# Car_Board.net
KiCad netlist of a schematic drawn in EAGLE
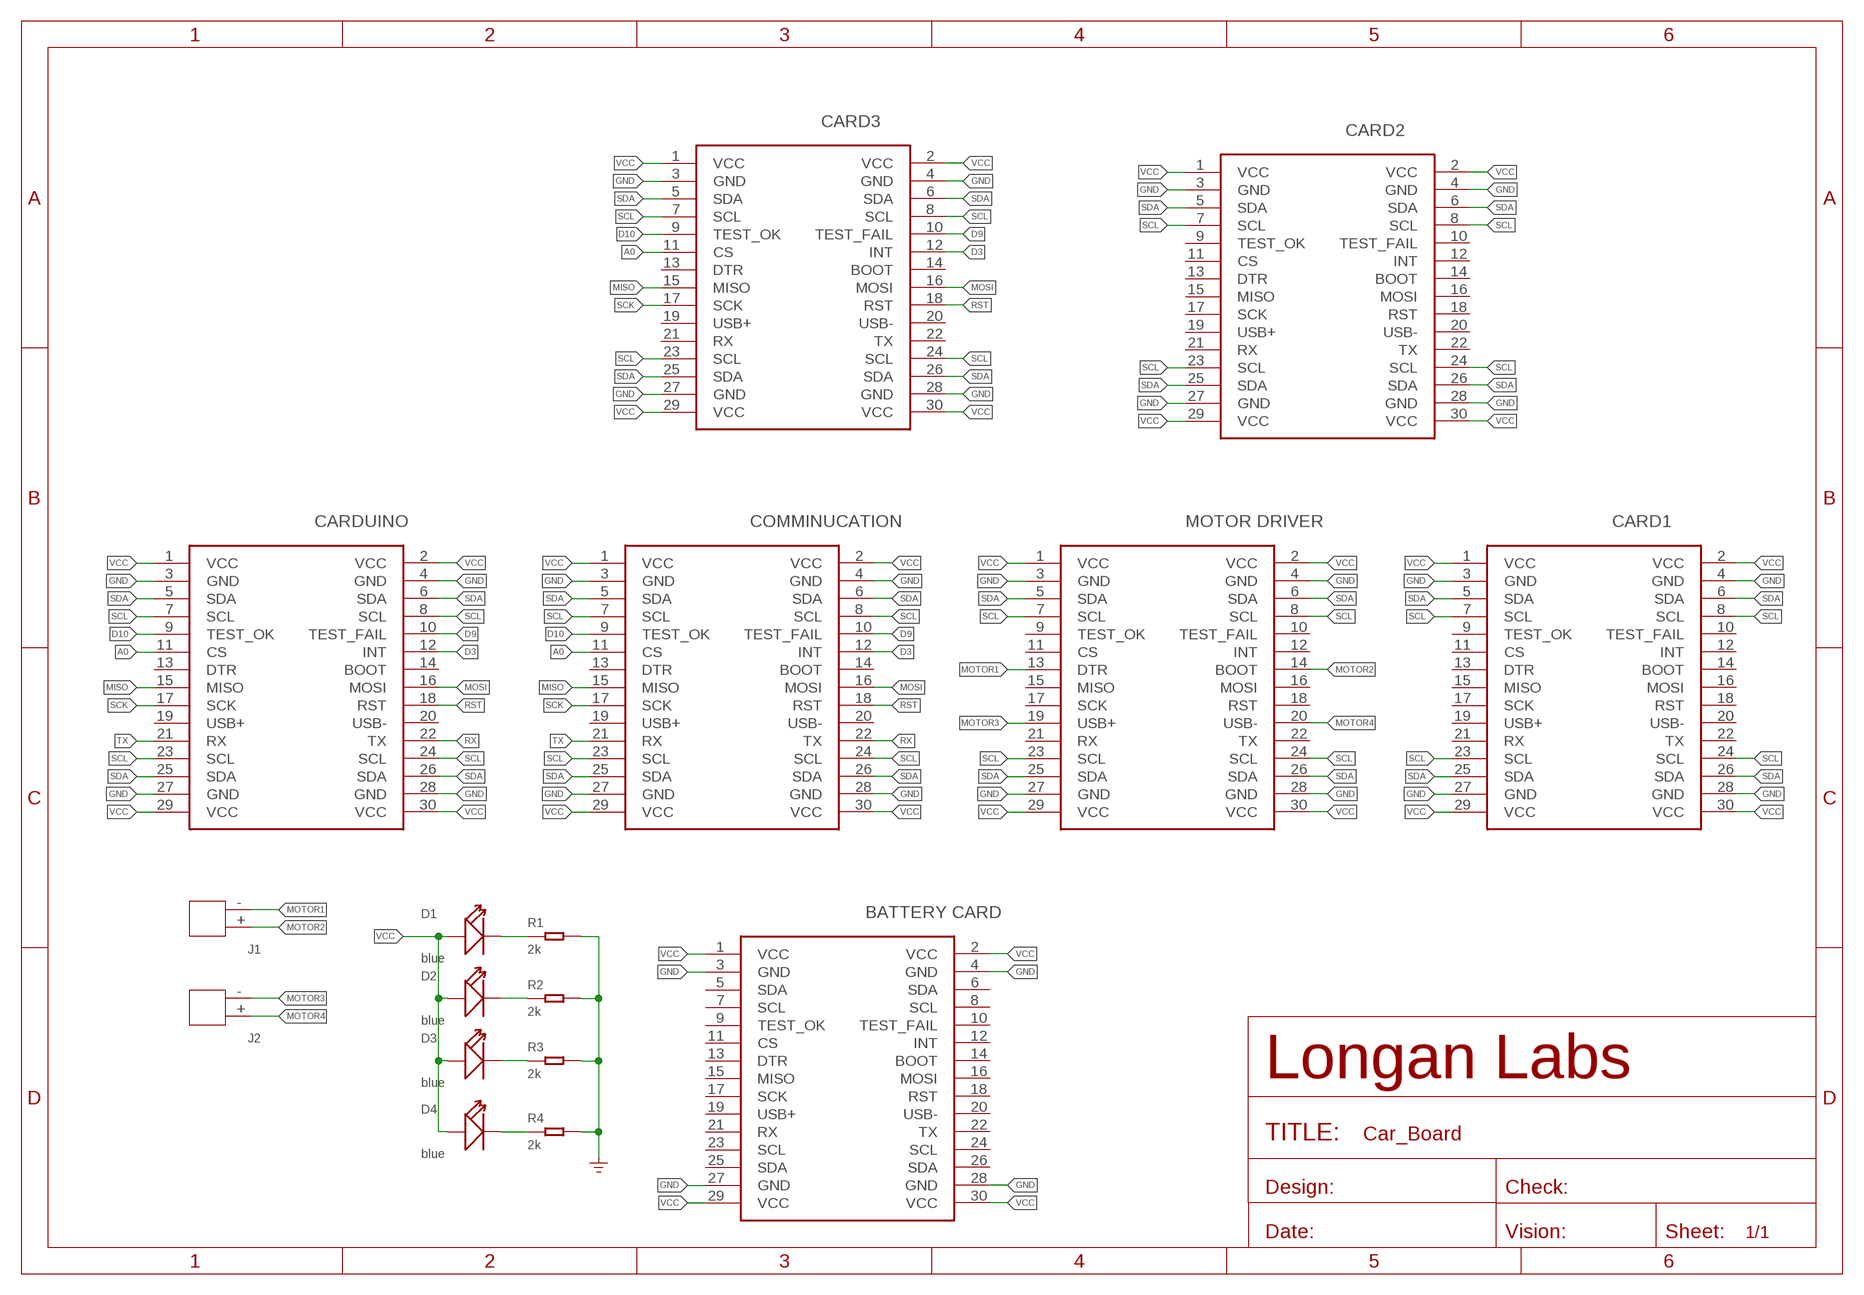
[diagram p0: schematic, sheet 1]

(export (version "E")
  (design (tool "Eeschema 10.0.6"))
  (components
    (comp (ref "CARDUINO")
      (value "CARDUINO")
      (footprint "eagle-import:2X15P-2.54")
      (libsource (lib "eagle-import") (part "MOUDLE-2X15P-2.54'2.54'"))
    )
    (comp (ref "CARDUINO1")
      (value "COMMINUCATION")
      (footprint "eagle-import:2X15P-2.54")
      (libsource (lib "eagle-import") (part "MOUDLE-2X15P-2.54'2.54'"))
    )
    (comp (ref "CARDUINO2")
      (value "MOTOR DRIVER")
      (footprint "eagle-import:2X15P-2.54")
      (libsource (lib "eagle-import") (part "MOUDLE-2X15P-2.54'2.54'"))
    )
    (comp (ref "CARDUINO3")
      (value "CARD1")
      (footprint "eagle-import:2X15P-2.54")
      (libsource (lib "eagle-import") (part "MOUDLE-2X15P-2.54'2.54'"))
    )
    (comp (ref "CARDUINO4")
      (value "CARD2")
      (footprint "eagle-import:2X15P-2.54")
      (libsource (lib "eagle-import") (part "MOUDLE-2X15P-2.54'2.54'"))
    )
    (comp (ref "CARDUINO5")
      (value "CARD3")
      (footprint "eagle-import:2X15P-2.54-90D")
      (libsource (lib "eagle-import") (part "MOUDLE-2X15P-2.54'90D'"))
    )
    (comp (ref "D1")
      (value "blue")
      (footprint "eagle-import:LED-0603")
      (libsource (lib "eagle-import") (part "LED'0603'"))
    )
    (comp (ref "D2")
      (value "blue")
      (footprint "eagle-import:LED-0603")
      (libsource (lib "eagle-import") (part "LED'0603'"))
    )
    (comp (ref "D3")
      (value "blue")
      (footprint "eagle-import:LED-0603")
      (libsource (lib "eagle-import") (part "LED'0603'"))
    )
    (comp (ref "D4")
      (value "blue")
      (footprint "eagle-import:LED-0603")
      (libsource (lib "eagle-import") (part "LED'0603'"))
    )
    (comp (ref "J1")
      (value "JST-2P-DIP'2.0'")
      (footprint "eagle-import:H2-2.0-6X4.5MM")
      (libsource (lib "eagle-import") (part "JST-2P-DIP'2.0'"))
    )
    (comp (ref "J2")
      (value "JST-2P-DIP'2.0'")
      (footprint "eagle-import:H2-2.0-6X4.5MM")
      (libsource (lib "eagle-import") (part "JST-2P-DIP'2.0'"))
    )
    (comp (ref "MOUDLE4")
      (value "BATTERY CARD")
      (footprint "eagle-import:2X15P-2.54")
      (libsource (lib "eagle-import") (part "MOUDLE-2X15P-2.54'2.54'"))
    )
    (comp (ref "R1")
      (value "2k")
      (footprint "eagle-import:R0603")
      (libsource (lib "eagle-import") (part "RES-0603"))
    )
    (comp (ref "R2")
      (value "2k")
      (footprint "eagle-import:R0603")
      (libsource (lib "eagle-import") (part "RES-0603"))
    )
    (comp (ref "R3")
      (value "2k")
      (footprint "eagle-import:R0603")
      (libsource (lib "eagle-import") (part "RES-0603"))
    )
    (comp (ref "R4")
      (value "2k")
      (footprint "eagle-import:R0603")
      (libsource (lib "eagle-import") (part "RES-0603"))
    )
  )
  (nets
    (net (code "1") (name "A0") (class "Default")
      (node (ref "CARDUINO") (pin "11") (pinfunction "CS_11") (pintype "bidirectional"))
      (node (ref "CARDUINO1") (pin "11") (pinfunction "CS_11") (pintype "bidirectional"))
      (node (ref "CARDUINO5") (pin "11") (pinfunction "CS_11") (pintype "bidirectional"))
    )
    (net (code "2") (name "D3") (class "Default")
      (node (ref "CARDUINO") (pin "12") (pinfunction "INT_12") (pintype "bidirectional"))
      (node (ref "CARDUINO1") (pin "12") (pinfunction "INT_12") (pintype "bidirectional"))
      (node (ref "CARDUINO5") (pin "12") (pinfunction "INT_12") (pintype "bidirectional"))
    )
    (net (code "3") (name "D9") (class "Default")
      (node (ref "CARDUINO") (pin "10") (pinfunction "TEST_FAIL_10") (pintype "bidirectional"))
      (node (ref "CARDUINO1") (pin "10") (pinfunction "TEST_FAIL_10") (pintype "bidirectional"))
      (node (ref "CARDUINO5") (pin "10") (pinfunction "TEST_FAIL_10") (pintype "bidirectional"))
    )
    (net (code "4") (name "D10") (class "Default")
      (node (ref "CARDUINO") (pin "9") (pinfunction "TEST_OK_9") (pintype "bidirectional"))
      (node (ref "CARDUINO1") (pin "9") (pinfunction "TEST_OK_9") (pintype "bidirectional"))
      (node (ref "CARDUINO5") (pin "9") (pinfunction "TEST_OK_9") (pintype "bidirectional"))
    )
    (net (code "5") (name "GND") (class "Default")
      (node (ref "CARDUINO") (pin "27") (pinfunction "GND_27") (pintype "bidirectional"))
      (node (ref "CARDUINO") (pin "28") (pinfunction "GND_28") (pintype "bidirectional"))
      (node (ref "CARDUINO") (pin "3") (pinfunction "GND_3") (pintype "bidirectional"))
      (node (ref "CARDUINO") (pin "4") (pinfunction "GND_4") (pintype "bidirectional"))
      (node (ref "CARDUINO1") (pin "27") (pinfunction "GND_27") (pintype "bidirectional"))
      (node (ref "CARDUINO1") (pin "28") (pinfunction "GND_28") (pintype "bidirectional"))
      (node (ref "CARDUINO1") (pin "3") (pinfunction "GND_3") (pintype "bidirectional"))
      (node (ref "CARDUINO1") (pin "4") (pinfunction "GND_4") (pintype "bidirectional"))
      (node (ref "CARDUINO2") (pin "27") (pinfunction "GND_27") (pintype "bidirectional"))
      (node (ref "CARDUINO2") (pin "28") (pinfunction "GND_28") (pintype "bidirectional"))
      (node (ref "CARDUINO2") (pin "3") (pinfunction "GND_3") (pintype "bidirectional"))
      (node (ref "CARDUINO2") (pin "4") (pinfunction "GND_4") (pintype "bidirectional"))
      (node (ref "CARDUINO3") (pin "27") (pinfunction "GND_27") (pintype "bidirectional"))
      (node (ref "CARDUINO3") (pin "28") (pinfunction "GND_28") (pintype "bidirectional"))
      (node (ref "CARDUINO3") (pin "3") (pinfunction "GND_3") (pintype "bidirectional"))
      (node (ref "CARDUINO3") (pin "4") (pinfunction "GND_4") (pintype "bidirectional"))
      (node (ref "CARDUINO4") (pin "27") (pinfunction "GND_27") (pintype "bidirectional"))
      (node (ref "CARDUINO4") (pin "28") (pinfunction "GND_28") (pintype "bidirectional"))
      (node (ref "CARDUINO4") (pin "3") (pinfunction "GND_3") (pintype "bidirectional"))
      (node (ref "CARDUINO4") (pin "4") (pinfunction "GND_4") (pintype "bidirectional"))
      (node (ref "CARDUINO5") (pin "27") (pinfunction "GND_27") (pintype "bidirectional"))
      (node (ref "CARDUINO5") (pin "28") (pinfunction "GND_28") (pintype "bidirectional"))
      (node (ref "CARDUINO5") (pin "3") (pinfunction "GND_3") (pintype "bidirectional"))
      (node (ref "CARDUINO5") (pin "4") (pinfunction "GND_4") (pintype "bidirectional"))
      (node (ref "MOUDLE4") (pin "27") (pinfunction "GND_27") (pintype "bidirectional"))
      (node (ref "MOUDLE4") (pin "28") (pinfunction "GND_28") (pintype "bidirectional"))
      (node (ref "MOUDLE4") (pin "3") (pinfunction "GND_3") (pintype "bidirectional"))
      (node (ref "MOUDLE4") (pin "4") (pinfunction "GND_4") (pintype "bidirectional"))
      (node (ref "R1") (pin "2") (pinfunction "2_2") (pintype "passive"))
      (node (ref "R2") (pin "2") (pinfunction "2_2") (pintype "passive"))
      (node (ref "R3") (pin "2") (pinfunction "2_2") (pintype "passive"))
      (node (ref "R4") (pin "2") (pinfunction "2_2") (pintype "passive"))
    )
    (net (code "6") (name "MISO") (class "Default")
      (node (ref "CARDUINO") (pin "15") (pinfunction "MISO_15") (pintype "bidirectional"))
      (node (ref "CARDUINO1") (pin "15") (pinfunction "MISO_15") (pintype "bidirectional"))
      (node (ref "CARDUINO5") (pin "15") (pinfunction "MISO_15") (pintype "bidirectional"))
    )
    (net (code "7") (name "MOSI") (class "Default")
      (node (ref "CARDUINO") (pin "16") (pinfunction "MOSI_16") (pintype "bidirectional"))
      (node (ref "CARDUINO1") (pin "16") (pinfunction "MOSI_16") (pintype "bidirectional"))
      (node (ref "CARDUINO5") (pin "16") (pinfunction "MOSI_16") (pintype "bidirectional"))
    )
    (net (code "8") (name "MOTOR1") (class "Default")
      (node (ref "CARDUINO2") (pin "13") (pinfunction "DTR_13") (pintype "bidirectional"))
      (node (ref "J1") (pin "-") (pinfunction "P$2_-") (pintype "bidirectional"))
    )
    (net (code "9") (name "MOTOR2") (class "Default")
      (node (ref "CARDUINO2") (pin "14") (pinfunction "BOOT_14") (pintype "bidirectional"))
      (node (ref "J1") (pin "+") (pinfunction "P$1_+") (pintype "bidirectional"))
    )
    (net (code "10") (name "MOTOR3") (class "Default")
      (node (ref "CARDUINO2") (pin "19") (pinfunction "USB+_19") (pintype "bidirectional"))
      (node (ref "J2") (pin "-") (pinfunction "P$2_-") (pintype "bidirectional"))
    )
    (net (code "11") (name "MOTOR4") (class "Default")
      (node (ref "CARDUINO2") (pin "20") (pinfunction "USB-_20") (pintype "bidirectional"))
      (node (ref "J2") (pin "+") (pinfunction "P$1_+") (pintype "bidirectional"))
    )
    (net (code "12") (name "Net-(D1-Pad-)") (class "Default")
      (node (ref "D1") (pin "-") (pinfunction "-_-") (pintype "passive"))
      (node (ref "R1") (pin "1") (pinfunction "1_1") (pintype "passive"))
    )
    (net (code "13") (name "Net-(D2-Pad-)") (class "Default")
      (node (ref "D2") (pin "-") (pinfunction "-_-") (pintype "passive"))
      (node (ref "R2") (pin "1") (pinfunction "1_1") (pintype "passive"))
    )
    (net (code "14") (name "Net-(D3-Pad-)") (class "Default")
      (node (ref "D3") (pin "-") (pinfunction "-_-") (pintype "passive"))
      (node (ref "R3") (pin "1") (pinfunction "1_1") (pintype "passive"))
    )
    (net (code "15") (name "Net-(D4-Pad-)") (class "Default")
      (node (ref "D4") (pin "-") (pinfunction "-_-") (pintype "passive"))
      (node (ref "R4") (pin "1") (pinfunction "1_1") (pintype "passive"))
    )
    (net (code "16") (name "RST") (class "Default")
      (node (ref "CARDUINO") (pin "18") (pinfunction "RST_18") (pintype "bidirectional"))
      (node (ref "CARDUINO1") (pin "18") (pinfunction "RST_18") (pintype "bidirectional"))
      (node (ref "CARDUINO5") (pin "18") (pinfunction "RST_18") (pintype "bidirectional"))
    )
    (net (code "17") (name "RX") (class "Default")
      (node (ref "CARDUINO") (pin "22") (pinfunction "TX_22") (pintype "bidirectional"))
      (node (ref "CARDUINO1") (pin "22") (pinfunction "TX_22") (pintype "bidirectional"))
    )
    (net (code "18") (name "SCK") (class "Default")
      (node (ref "CARDUINO") (pin "17") (pinfunction "SCK_17") (pintype "bidirectional"))
      (node (ref "CARDUINO1") (pin "17") (pinfunction "SCK_17") (pintype "bidirectional"))
      (node (ref "CARDUINO5") (pin "17") (pinfunction "SCK_17") (pintype "bidirectional"))
    )
    (net (code "19") (name "SCL") (class "Default")
      (node (ref "CARDUINO") (pin "23") (pinfunction "SCL_23") (pintype "bidirectional"))
      (node (ref "CARDUINO") (pin "24") (pinfunction "SCL_24") (pintype "bidirectional"))
      (node (ref "CARDUINO") (pin "7") (pinfunction "SCL_7") (pintype "bidirectional"))
      (node (ref "CARDUINO") (pin "8") (pinfunction "SCL_8") (pintype "bidirectional"))
      (node (ref "CARDUINO1") (pin "23") (pinfunction "SCL_23") (pintype "bidirectional"))
      (node (ref "CARDUINO1") (pin "24") (pinfunction "SCL_24") (pintype "bidirectional"))
      (node (ref "CARDUINO1") (pin "7") (pinfunction "SCL_7") (pintype "bidirectional"))
      (node (ref "CARDUINO1") (pin "8") (pinfunction "SCL_8") (pintype "bidirectional"))
      (node (ref "CARDUINO2") (pin "23") (pinfunction "SCL_23") (pintype "bidirectional"))
      (node (ref "CARDUINO2") (pin "24") (pinfunction "SCL_24") (pintype "bidirectional"))
      (node (ref "CARDUINO2") (pin "7") (pinfunction "SCL_7") (pintype "bidirectional"))
      (node (ref "CARDUINO2") (pin "8") (pinfunction "SCL_8") (pintype "bidirectional"))
      (node (ref "CARDUINO3") (pin "23") (pinfunction "SCL_23") (pintype "bidirectional"))
      (node (ref "CARDUINO3") (pin "24") (pinfunction "SCL_24") (pintype "bidirectional"))
      (node (ref "CARDUINO3") (pin "7") (pinfunction "SCL_7") (pintype "bidirectional"))
      (node (ref "CARDUINO3") (pin "8") (pinfunction "SCL_8") (pintype "bidirectional"))
      (node (ref "CARDUINO4") (pin "23") (pinfunction "SCL_23") (pintype "bidirectional"))
      (node (ref "CARDUINO4") (pin "24") (pinfunction "SCL_24") (pintype "bidirectional"))
      (node (ref "CARDUINO4") (pin "7") (pinfunction "SCL_7") (pintype "bidirectional"))
      (node (ref "CARDUINO4") (pin "8") (pinfunction "SCL_8") (pintype "bidirectional"))
      (node (ref "CARDUINO5") (pin "23") (pinfunction "SCL_23") (pintype "bidirectional"))
      (node (ref "CARDUINO5") (pin "24") (pinfunction "SCL_24") (pintype "bidirectional"))
      (node (ref "CARDUINO5") (pin "7") (pinfunction "SCL_7") (pintype "bidirectional"))
      (node (ref "CARDUINO5") (pin "8") (pinfunction "SCL_8") (pintype "bidirectional"))
    )
    (net (code "20") (name "SDA") (class "Default")
      (node (ref "CARDUINO") (pin "25") (pinfunction "SDA_25") (pintype "bidirectional"))
      (node (ref "CARDUINO") (pin "26") (pinfunction "SDA_26") (pintype "bidirectional"))
      (node (ref "CARDUINO") (pin "5") (pinfunction "SDA_5") (pintype "bidirectional"))
      (node (ref "CARDUINO") (pin "6") (pinfunction "SDA_6") (pintype "bidirectional"))
      (node (ref "CARDUINO1") (pin "25") (pinfunction "SDA_25") (pintype "bidirectional"))
      (node (ref "CARDUINO1") (pin "26") (pinfunction "SDA_26") (pintype "bidirectional"))
      (node (ref "CARDUINO1") (pin "5") (pinfunction "SDA_5") (pintype "bidirectional"))
      (node (ref "CARDUINO1") (pin "6") (pinfunction "SDA_6") (pintype "bidirectional"))
      (node (ref "CARDUINO2") (pin "25") (pinfunction "SDA_25") (pintype "bidirectional"))
      (node (ref "CARDUINO2") (pin "26") (pinfunction "SDA_26") (pintype "bidirectional"))
      (node (ref "CARDUINO2") (pin "5") (pinfunction "SDA_5") (pintype "bidirectional"))
      (node (ref "CARDUINO2") (pin "6") (pinfunction "SDA_6") (pintype "bidirectional"))
      (node (ref "CARDUINO3") (pin "25") (pinfunction "SDA_25") (pintype "bidirectional"))
      (node (ref "CARDUINO3") (pin "26") (pinfunction "SDA_26") (pintype "bidirectional"))
      (node (ref "CARDUINO3") (pin "5") (pinfunction "SDA_5") (pintype "bidirectional"))
      (node (ref "CARDUINO3") (pin "6") (pinfunction "SDA_6") (pintype "bidirectional"))
      (node (ref "CARDUINO4") (pin "25") (pinfunction "SDA_25") (pintype "bidirectional"))
      (node (ref "CARDUINO4") (pin "26") (pinfunction "SDA_26") (pintype "bidirectional"))
      (node (ref "CARDUINO4") (pin "5") (pinfunction "SDA_5") (pintype "bidirectional"))
      (node (ref "CARDUINO4") (pin "6") (pinfunction "SDA_6") (pintype "bidirectional"))
      (node (ref "CARDUINO5") (pin "25") (pinfunction "SDA_25") (pintype "bidirectional"))
      (node (ref "CARDUINO5") (pin "26") (pinfunction "SDA_26") (pintype "bidirectional"))
      (node (ref "CARDUINO5") (pin "5") (pinfunction "SDA_5") (pintype "bidirectional"))
      (node (ref "CARDUINO5") (pin "6") (pinfunction "SDA_6") (pintype "bidirectional"))
    )
    (net (code "21") (name "TX") (class "Default")
      (node (ref "CARDUINO") (pin "21") (pinfunction "RX_21") (pintype "bidirectional"))
      (node (ref "CARDUINO1") (pin "21") (pinfunction "RX_21") (pintype "bidirectional"))
    )
    (net (code "22") (name "VCC") (class "Default")
      (node (ref "CARDUINO") (pin "1") (pinfunction "VCC_1") (pintype "bidirectional"))
      (node (ref "CARDUINO") (pin "2") (pinfunction "VCC_2") (pintype "bidirectional"))
      (node (ref "CARDUINO") (pin "29") (pinfunction "VCC_29") (pintype "bidirectional"))
      (node (ref "CARDUINO") (pin "30") (pinfunction "VCC_30") (pintype "bidirectional"))
      (node (ref "CARDUINO1") (pin "1") (pinfunction "VCC_1") (pintype "bidirectional"))
      (node (ref "CARDUINO1") (pin "2") (pinfunction "VCC_2") (pintype "bidirectional"))
      (node (ref "CARDUINO1") (pin "29") (pinfunction "VCC_29") (pintype "bidirectional"))
      (node (ref "CARDUINO1") (pin "30") (pinfunction "VCC_30") (pintype "bidirectional"))
      (node (ref "CARDUINO2") (pin "1") (pinfunction "VCC_1") (pintype "bidirectional"))
      (node (ref "CARDUINO2") (pin "2") (pinfunction "VCC_2") (pintype "bidirectional"))
      (node (ref "CARDUINO2") (pin "29") (pinfunction "VCC_29") (pintype "bidirectional"))
      (node (ref "CARDUINO2") (pin "30") (pinfunction "VCC_30") (pintype "bidirectional"))
      (node (ref "CARDUINO3") (pin "1") (pinfunction "VCC_1") (pintype "bidirectional"))
      (node (ref "CARDUINO3") (pin "2") (pinfunction "VCC_2") (pintype "bidirectional"))
      (node (ref "CARDUINO3") (pin "29") (pinfunction "VCC_29") (pintype "bidirectional"))
      (node (ref "CARDUINO3") (pin "30") (pinfunction "VCC_30") (pintype "bidirectional"))
      (node (ref "CARDUINO4") (pin "1") (pinfunction "VCC_1") (pintype "bidirectional"))
      (node (ref "CARDUINO4") (pin "2") (pinfunction "VCC_2") (pintype "bidirectional"))
      (node (ref "CARDUINO4") (pin "29") (pinfunction "VCC_29") (pintype "bidirectional"))
      (node (ref "CARDUINO4") (pin "30") (pinfunction "VCC_30") (pintype "bidirectional"))
      (node (ref "CARDUINO5") (pin "1") (pinfunction "VCC_1") (pintype "bidirectional"))
      (node (ref "CARDUINO5") (pin "2") (pinfunction "VCC_2") (pintype "bidirectional"))
      (node (ref "CARDUINO5") (pin "29") (pinfunction "VCC_29") (pintype "bidirectional"))
      (node (ref "CARDUINO5") (pin "30") (pinfunction "VCC_30") (pintype "bidirectional"))
      (node (ref "D1") (pin "+") (pinfunction "+_+") (pintype "passive"))
      (node (ref "D2") (pin "+") (pinfunction "+_+") (pintype "passive"))
      (node (ref "D3") (pin "+") (pinfunction "+_+") (pintype "passive"))
      (node (ref "D4") (pin "+") (pinfunction "+_+") (pintype "passive"))
      (node (ref "MOUDLE4") (pin "1") (pinfunction "VCC_1") (pintype "bidirectional"))
      (node (ref "MOUDLE4") (pin "2") (pinfunction "VCC_2") (pintype "bidirectional"))
      (node (ref "MOUDLE4") (pin "29") (pinfunction "VCC_29") (pintype "bidirectional"))
      (node (ref "MOUDLE4") (pin "30") (pinfunction "VCC_30") (pintype "bidirectional"))
    )
    (net (code "23") (name "unconnected-(CARDUINO-BOOT-Pad14)") (class "Default")
      (node (ref "CARDUINO") (pin "14") (pinfunction "BOOT_14") (pintype "bidirectional"))
    )
    (net (code "24") (name "unconnected-(CARDUINO-DTR-Pad13)") (class "Default")
      (node (ref "CARDUINO") (pin "13") (pinfunction "DTR_13") (pintype "bidirectional"))
    )
    (net (code "25") (name "unconnected-(CARDUINO-USB+-Pad19)") (class "Default")
      (node (ref "CARDUINO") (pin "19") (pinfunction "USB+_19") (pintype "bidirectional"))
    )
    (net (code "26") (name "unconnected-(CARDUINO-USB--Pad20)") (class "Default")
      (node (ref "CARDUINO") (pin "20") (pinfunction "USB-_20") (pintype "bidirectional"))
    )
    (net (code "27") (name "unconnected-(CARDUINO1-BOOT-Pad14)") (class "Default")
      (node (ref "CARDUINO1") (pin "14") (pinfunction "BOOT_14") (pintype "bidirectional"))
    )
    (net (code "28") (name "unconnected-(CARDUINO1-DTR-Pad13)") (class "Default")
      (node (ref "CARDUINO1") (pin "13") (pinfunction "DTR_13") (pintype "bidirectional"))
    )
    (net (code "29") (name "unconnected-(CARDUINO1-USB+-Pad19)") (class "Default")
      (node (ref "CARDUINO1") (pin "19") (pinfunction "USB+_19") (pintype "bidirectional"))
    )
    (net (code "30") (name "unconnected-(CARDUINO1-USB--Pad20)") (class "Default")
      (node (ref "CARDUINO1") (pin "20") (pinfunction "USB-_20") (pintype "bidirectional"))
    )
    (net (code "31") (name "unconnected-(CARDUINO2-CS-Pad11)") (class "Default")
      (node (ref "CARDUINO2") (pin "11") (pinfunction "CS_11") (pintype "bidirectional"))
    )
    (net (code "32") (name "unconnected-(CARDUINO2-INT-Pad12)") (class "Default")
      (node (ref "CARDUINO2") (pin "12") (pinfunction "INT_12") (pintype "bidirectional"))
    )
    (net (code "33") (name "unconnected-(CARDUINO2-MISO-Pad15)") (class "Default")
      (node (ref "CARDUINO2") (pin "15") (pinfunction "MISO_15") (pintype "bidirectional"))
    )
    (net (code "34") (name "unconnected-(CARDUINO2-MOSI-Pad16)") (class "Default")
      (node (ref "CARDUINO2") (pin "16") (pinfunction "MOSI_16") (pintype "bidirectional"))
    )
    (net (code "35") (name "unconnected-(CARDUINO2-RST-Pad18)") (class "Default")
      (node (ref "CARDUINO2") (pin "18") (pinfunction "RST_18") (pintype "bidirectional"))
    )
    (net (code "36") (name "unconnected-(CARDUINO2-RX-Pad21)") (class "Default")
      (node (ref "CARDUINO2") (pin "21") (pinfunction "RX_21") (pintype "bidirectional"))
    )
    (net (code "37") (name "unconnected-(CARDUINO2-SCK-Pad17)") (class "Default")
      (node (ref "CARDUINO2") (pin "17") (pinfunction "SCK_17") (pintype "bidirectional"))
    )
    (net (code "38") (name "unconnected-(CARDUINO2-TEST_FAIL-Pad10)") (class "Default")
      (node (ref "CARDUINO2") (pin "10") (pinfunction "TEST_FAIL_10") (pintype "bidirectional"))
    )
    (net (code "39") (name "unconnected-(CARDUINO2-TEST_OK-Pad9)") (class "Default")
      (node (ref "CARDUINO2") (pin "9") (pinfunction "TEST_OK_9") (pintype "bidirectional"))
    )
    (net (code "40") (name "unconnected-(CARDUINO2-TX-Pad22)") (class "Default")
      (node (ref "CARDUINO2") (pin "22") (pinfunction "TX_22") (pintype "bidirectional"))
    )
    (net (code "41") (name "unconnected-(CARDUINO3-BOOT-Pad14)") (class "Default")
      (node (ref "CARDUINO3") (pin "14") (pinfunction "BOOT_14") (pintype "bidirectional"))
    )
    (net (code "42") (name "unconnected-(CARDUINO3-CS-Pad11)") (class "Default")
      (node (ref "CARDUINO3") (pin "11") (pinfunction "CS_11") (pintype "bidirectional"))
    )
    (net (code "43") (name "unconnected-(CARDUINO3-DTR-Pad13)") (class "Default")
      (node (ref "CARDUINO3") (pin "13") (pinfunction "DTR_13") (pintype "bidirectional"))
    )
    (net (code "44") (name "unconnected-(CARDUINO3-INT-Pad12)") (class "Default")
      (node (ref "CARDUINO3") (pin "12") (pinfunction "INT_12") (pintype "bidirectional"))
    )
    (net (code "45") (name "unconnected-(CARDUINO3-MISO-Pad15)") (class "Default")
      (node (ref "CARDUINO3") (pin "15") (pinfunction "MISO_15") (pintype "bidirectional"))
    )
    (net (code "46") (name "unconnected-(CARDUINO3-MOSI-Pad16)") (class "Default")
      (node (ref "CARDUINO3") (pin "16") (pinfunction "MOSI_16") (pintype "bidirectional"))
    )
    (net (code "47") (name "unconnected-(CARDUINO3-RST-Pad18)") (class "Default")
      (node (ref "CARDUINO3") (pin "18") (pinfunction "RST_18") (pintype "bidirectional"))
    )
    (net (code "48") (name "unconnected-(CARDUINO3-RX-Pad21)") (class "Default")
      (node (ref "CARDUINO3") (pin "21") (pinfunction "RX_21") (pintype "bidirectional"))
    )
    (net (code "49") (name "unconnected-(CARDUINO3-SCK-Pad17)") (class "Default")
      (node (ref "CARDUINO3") (pin "17") (pinfunction "SCK_17") (pintype "bidirectional"))
    )
    (net (code "50") (name "unconnected-(CARDUINO3-TEST_FAIL-Pad10)") (class "Default")
      (node (ref "CARDUINO3") (pin "10") (pinfunction "TEST_FAIL_10") (pintype "bidirectional"))
    )
    (net (code "51") (name "unconnected-(CARDUINO3-TEST_OK-Pad9)") (class "Default")
      (node (ref "CARDUINO3") (pin "9") (pinfunction "TEST_OK_9") (pintype "bidirectional"))
    )
    (net (code "52") (name "unconnected-(CARDUINO3-TX-Pad22)") (class "Default")
      (node (ref "CARDUINO3") (pin "22") (pinfunction "TX_22") (pintype "bidirectional"))
    )
    (net (code "53") (name "unconnected-(CARDUINO3-USB+-Pad19)") (class "Default")
      (node (ref "CARDUINO3") (pin "19") (pinfunction "USB+_19") (pintype "bidirectional"))
    )
    (net (code "54") (name "unconnected-(CARDUINO3-USB--Pad20)") (class "Default")
      (node (ref "CARDUINO3") (pin "20") (pinfunction "USB-_20") (pintype "bidirectional"))
    )
    (net (code "55") (name "unconnected-(CARDUINO4-BOOT-Pad14)") (class "Default")
      (node (ref "CARDUINO4") (pin "14") (pinfunction "BOOT_14") (pintype "bidirectional"))
    )
    (net (code "56") (name "unconnected-(CARDUINO4-CS-Pad11)") (class "Default")
      (node (ref "CARDUINO4") (pin "11") (pinfunction "CS_11") (pintype "bidirectional"))
    )
    (net (code "57") (name "unconnected-(CARDUINO4-DTR-Pad13)") (class "Default")
      (node (ref "CARDUINO4") (pin "13") (pinfunction "DTR_13") (pintype "bidirectional"))
    )
    (net (code "58") (name "unconnected-(CARDUINO4-INT-Pad12)") (class "Default")
      (node (ref "CARDUINO4") (pin "12") (pinfunction "INT_12") (pintype "bidirectional"))
    )
    (net (code "59") (name "unconnected-(CARDUINO4-MISO-Pad15)") (class "Default")
      (node (ref "CARDUINO4") (pin "15") (pinfunction "MISO_15") (pintype "bidirectional"))
    )
    (net (code "60") (name "unconnected-(CARDUINO4-MOSI-Pad16)") (class "Default")
      (node (ref "CARDUINO4") (pin "16") (pinfunction "MOSI_16") (pintype "bidirectional"))
    )
    (net (code "61") (name "unconnected-(CARDUINO4-RST-Pad18)") (class "Default")
      (node (ref "CARDUINO4") (pin "18") (pinfunction "RST_18") (pintype "bidirectional"))
    )
    (net (code "62") (name "unconnected-(CARDUINO4-RX-Pad21)") (class "Default")
      (node (ref "CARDUINO4") (pin "21") (pinfunction "RX_21") (pintype "bidirectional"))
    )
    (net (code "63") (name "unconnected-(CARDUINO4-SCK-Pad17)") (class "Default")
      (node (ref "CARDUINO4") (pin "17") (pinfunction "SCK_17") (pintype "bidirectional"))
    )
    (net (code "64") (name "unconnected-(CARDUINO4-TEST_FAIL-Pad10)") (class "Default")
      (node (ref "CARDUINO4") (pin "10") (pinfunction "TEST_FAIL_10") (pintype "bidirectional"))
    )
    (net (code "65") (name "unconnected-(CARDUINO4-TEST_OK-Pad9)") (class "Default")
      (node (ref "CARDUINO4") (pin "9") (pinfunction "TEST_OK_9") (pintype "bidirectional"))
    )
    (net (code "66") (name "unconnected-(CARDUINO4-TX-Pad22)") (class "Default")
      (node (ref "CARDUINO4") (pin "22") (pinfunction "TX_22") (pintype "bidirectional"))
    )
    (net (code "67") (name "unconnected-(CARDUINO4-USB+-Pad19)") (class "Default")
      (node (ref "CARDUINO4") (pin "19") (pinfunction "USB+_19") (pintype "bidirectional"))
    )
    (net (code "68") (name "unconnected-(CARDUINO4-USB--Pad20)") (class "Default")
      (node (ref "CARDUINO4") (pin "20") (pinfunction "USB-_20") (pintype "bidirectional"))
    )
    (net (code "69") (name "unconnected-(CARDUINO5-BOOT-Pad14)") (class "Default")
      (node (ref "CARDUINO5") (pin "14") (pinfunction "BOOT_14") (pintype "bidirectional"))
    )
    (net (code "70") (name "unconnected-(CARDUINO5-DTR-Pad13)") (class "Default")
      (node (ref "CARDUINO5") (pin "13") (pinfunction "DTR_13") (pintype "bidirectional"))
    )
    (net (code "71") (name "unconnected-(CARDUINO5-RX-Pad21)") (class "Default")
      (node (ref "CARDUINO5") (pin "21") (pinfunction "RX_21") (pintype "bidirectional"))
    )
    (net (code "72") (name "unconnected-(CARDUINO5-TX-Pad22)") (class "Default")
      (node (ref "CARDUINO5") (pin "22") (pinfunction "TX_22") (pintype "bidirectional"))
    )
    (net (code "73") (name "unconnected-(CARDUINO5-USB+-Pad19)") (class "Default")
      (node (ref "CARDUINO5") (pin "19") (pinfunction "USB+_19") (pintype "bidirectional"))
    )
    (net (code "74") (name "unconnected-(CARDUINO5-USB--Pad20)") (class "Default")
      (node (ref "CARDUINO5") (pin "20") (pinfunction "USB-_20") (pintype "bidirectional"))
    )
    (net (code "75") (name "unconnected-(MOUDLE4-BOOT-Pad14)") (class "Default")
      (node (ref "MOUDLE4") (pin "14") (pinfunction "BOOT_14") (pintype "bidirectional"))
    )
    (net (code "76") (name "unconnected-(MOUDLE4-CS-Pad11)") (class "Default")
      (node (ref "MOUDLE4") (pin "11") (pinfunction "CS_11") (pintype "bidirectional"))
    )
    (net (code "77") (name "unconnected-(MOUDLE4-DTR-Pad13)") (class "Default")
      (node (ref "MOUDLE4") (pin "13") (pinfunction "DTR_13") (pintype "bidirectional"))
    )
    (net (code "78") (name "unconnected-(MOUDLE4-INT-Pad12)") (class "Default")
      (node (ref "MOUDLE4") (pin "12") (pinfunction "INT_12") (pintype "bidirectional"))
    )
    (net (code "79") (name "unconnected-(MOUDLE4-MISO-Pad15)") (class "Default")
      (node (ref "MOUDLE4") (pin "15") (pinfunction "MISO_15") (pintype "bidirectional"))
    )
    (net (code "80") (name "unconnected-(MOUDLE4-MOSI-Pad16)") (class "Default")
      (node (ref "MOUDLE4") (pin "16") (pinfunction "MOSI_16") (pintype "bidirectional"))
    )
    (net (code "81") (name "unconnected-(MOUDLE4-RST-Pad18)") (class "Default")
      (node (ref "MOUDLE4") (pin "18") (pinfunction "RST_18") (pintype "bidirectional"))
    )
    (net (code "82") (name "unconnected-(MOUDLE4-RX-Pad21)") (class "Default")
      (node (ref "MOUDLE4") (pin "21") (pinfunction "RX_21") (pintype "bidirectional"))
    )
    (net (code "83") (name "unconnected-(MOUDLE4-SCK-Pad17)") (class "Default")
      (node (ref "MOUDLE4") (pin "17") (pinfunction "SCK_17") (pintype "bidirectional"))
    )
    (net (code "84") (name "unconnected-(MOUDLE4-SCL-Pad7)") (class "Default")
      (node (ref "MOUDLE4") (pin "7") (pinfunction "SCL_7") (pintype "bidirectional"))
    )
    (net (code "85") (name "unconnected-(MOUDLE4-SCL-Pad8)") (class "Default")
      (node (ref "MOUDLE4") (pin "8") (pinfunction "SCL_8") (pintype "bidirectional"))
    )
    (net (code "86") (name "unconnected-(MOUDLE4-SCL-Pad23)") (class "Default")
      (node (ref "MOUDLE4") (pin "23") (pinfunction "SCL_23") (pintype "bidirectional"))
    )
    (net (code "87") (name "unconnected-(MOUDLE4-SCL-Pad24)") (class "Default")
      (node (ref "MOUDLE4") (pin "24") (pinfunction "SCL_24") (pintype "bidirectional"))
    )
    (net (code "88") (name "unconnected-(MOUDLE4-SDA-Pad5)") (class "Default")
      (node (ref "MOUDLE4") (pin "5") (pinfunction "SDA_5") (pintype "bidirectional"))
    )
    (net (code "89") (name "unconnected-(MOUDLE4-SDA-Pad6)") (class "Default")
      (node (ref "MOUDLE4") (pin "6") (pinfunction "SDA_6") (pintype "bidirectional"))
    )
    (net (code "90") (name "unconnected-(MOUDLE4-SDA-Pad25)") (class "Default")
      (node (ref "MOUDLE4") (pin "25") (pinfunction "SDA_25") (pintype "bidirectional"))
    )
    (net (code "91") (name "unconnected-(MOUDLE4-SDA-Pad26)") (class "Default")
      (node (ref "MOUDLE4") (pin "26") (pinfunction "SDA_26") (pintype "bidirectional"))
    )
    (net (code "92") (name "unconnected-(MOUDLE4-TEST_FAIL-Pad10)") (class "Default")
      (node (ref "MOUDLE4") (pin "10") (pinfunction "TEST_FAIL_10") (pintype "bidirectional"))
    )
    (net (code "93") (name "unconnected-(MOUDLE4-TEST_OK-Pad9)") (class "Default")
      (node (ref "MOUDLE4") (pin "9") (pinfunction "TEST_OK_9") (pintype "bidirectional"))
    )
    (net (code "94") (name "unconnected-(MOUDLE4-TX-Pad22)") (class "Default")
      (node (ref "MOUDLE4") (pin "22") (pinfunction "TX_22") (pintype "bidirectional"))
    )
    (net (code "95") (name "unconnected-(MOUDLE4-USB+-Pad19)") (class "Default")
      (node (ref "MOUDLE4") (pin "19") (pinfunction "USB+_19") (pintype "bidirectional"))
    )
    (net (code "96") (name "unconnected-(MOUDLE4-USB--Pad20)") (class "Default")
      (node (ref "MOUDLE4") (pin "20") (pinfunction "USB-_20") (pintype "bidirectional"))
    )
  )
)
